# SW6106_A_A_B_C_MCU_SEG.net
KiCad netlist of a schematic drawn in Altium Designer
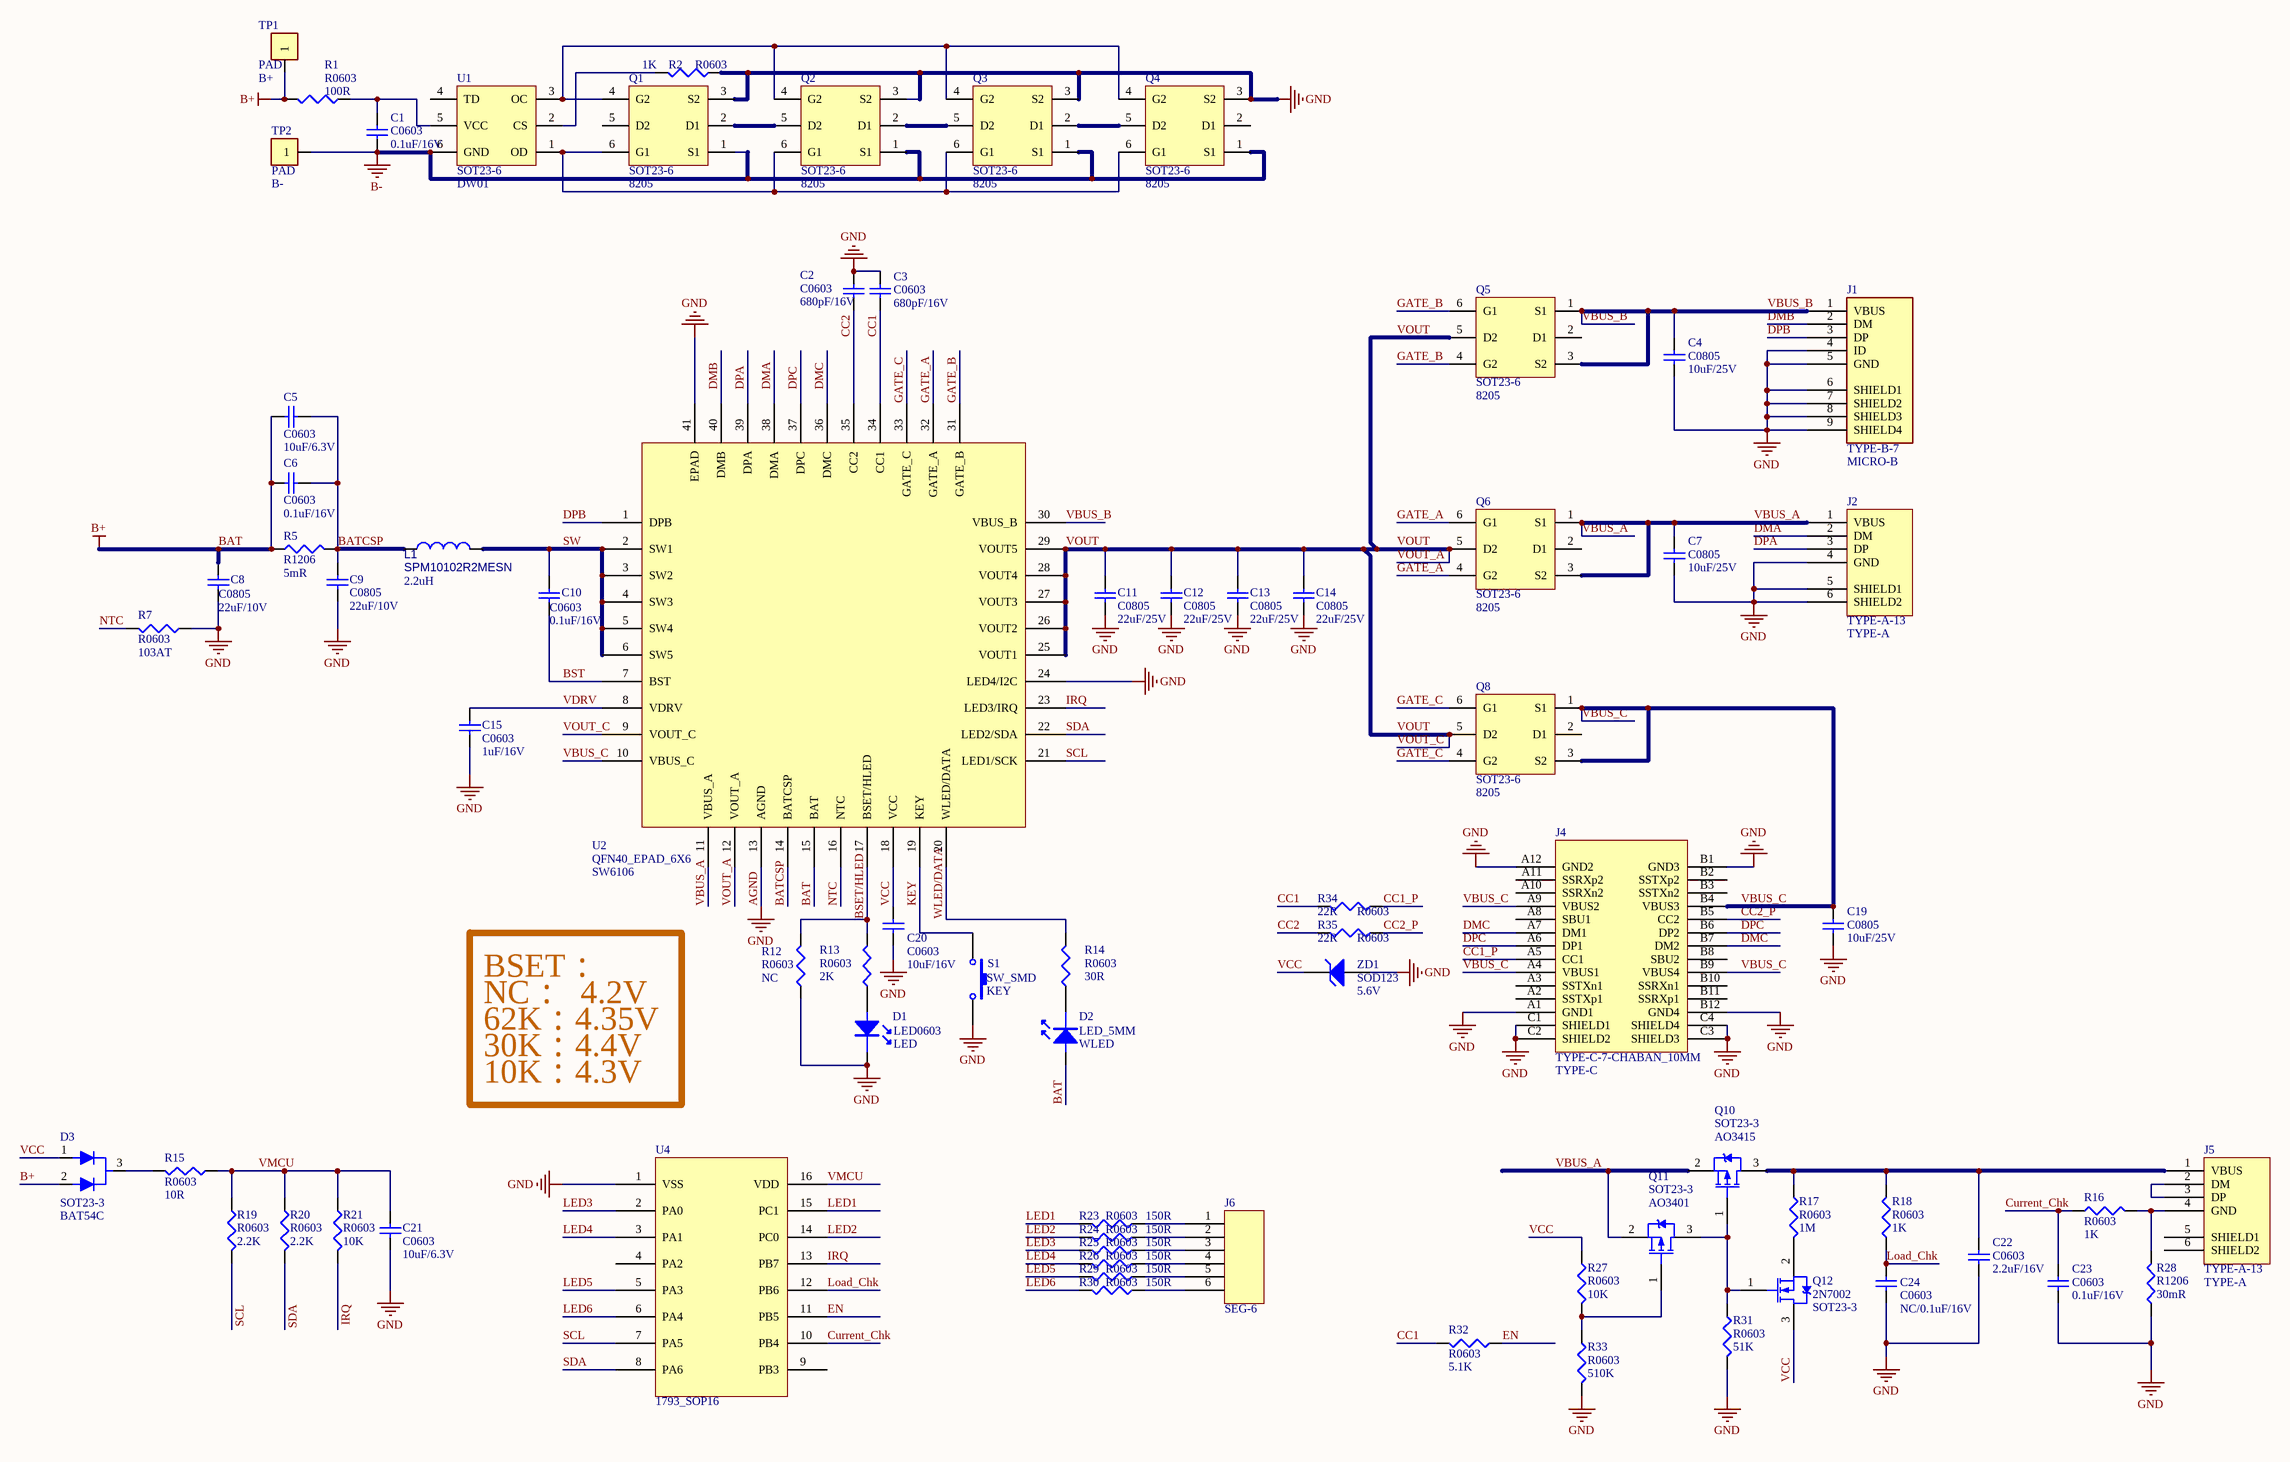
[diagram p0: SW6106+A+A+B+C+MCU+SEG.SchDoc]

(export (version "E")
  (design (tool "Eeschema 10.0.6"))
  (components
    (comp (ref "C1")
      (value "C0603")
      (footprint "C0603")
      (description "Capacitor")
      (fields (field (name "ALTIUM_VALUE") "0.1uF/16V") (field (name "PUBLISHER") "Altium Limited"))
      (libsource (lib "*") (part "Cap"))
    )
    (comp (ref "C2")
      (value "C0603")
      (footprint "C0603")
      (description "Capacitor")
      (fields (field (name "ALTIUM_VALUE") "680pF/16V") (field (name "PUBLISHER") "Altium Limited"))
      (libsource (lib "*") (part "CAP0603"))
    )
    (comp (ref "C3")
      (value "C0603")
      (footprint "C0603")
      (description "Capacitor")
      (fields (field (name "ALTIUM_VALUE") "680pF/16V") (field (name "PUBLISHER") "Altium Limited"))
      (libsource (lib "*") (part "CAP0603"))
    )
    (comp (ref "C4")
      (value "C0805")
      (footprint "C0805")
      (description "Capacitor")
      (fields (field (name "ALTIUM_VALUE") "10uF/25V") (field (name "PUBLISHER") "Altium Limited"))
      (libsource (lib "*") (part "CAP0603"))
    )
    (comp (ref "C5")
      (value "C0603")
      (footprint "C0603")
      (description "Capacitor")
      (fields (field (name "ALTIUM_VALUE") "10uF/6.3V") (field (name "PUBLISHER") "Altium Limited"))
      (libsource (lib "*") (part "CAP0603"))
    )
    (comp (ref "C6")
      (value "C0603")
      (footprint "C0603")
      (description "Capacitor")
      (fields (field (name "ALTIUM_VALUE") "0.1uF/16V") (field (name "PUBLISHER") "Altium Limited"))
      (libsource (lib "*") (part "CAP0603"))
    )
    (comp (ref "C7")
      (value "C0805")
      (footprint "C0805")
      (description "Capacitor")
      (fields (field (name "ALTIUM_VALUE") "10uF/25V") (field (name "PUBLISHER") "Altium Limited"))
      (libsource (lib "*") (part "CAP0603"))
    )
    (comp (ref "C8")
      (value "C0805")
      (footprint "C0805")
      (description "Capacitor")
      (fields (field (name "ALTIUM_VALUE") "22uF/10V") (field (name "PUBLISHER") "Altium Limited"))
      (libsource (lib "*") (part "CAP0805"))
    )
    (comp (ref "C9")
      (value "C0805")
      (footprint "C0805")
      (description "Capacitor")
      (fields (field (name "ALTIUM_VALUE") "22uF/10V") (field (name "PUBLISHER") "Altium Limited"))
      (libsource (lib "*") (part "CAP0805"))
    )
    (comp (ref "C10")
      (value "C0603")
      (footprint "C0603")
      (description "Capacitor")
      (fields (field (name "ALTIUM_VALUE") "0.1uF/16V") (field (name "PUBLISHER") "Altium Limited"))
      (libsource (lib "*") (part "CAP0603"))
    )
    (comp (ref "C11")
      (value "C0805")
      (footprint "C0805")
      (description "Capacitor")
      (fields (field (name "ALTIUM_VALUE") "22uF/25V") (field (name "PUBLISHER") "Altium Limited"))
      (libsource (lib "*") (part "CAP0805"))
    )
    (comp (ref "C12")
      (value "C0805")
      (footprint "C0805")
      (description "Capacitor")
      (fields (field (name "ALTIUM_VALUE") "22uF/25V") (field (name "PUBLISHER") "Altium Limited"))
      (libsource (lib "*") (part "CAP0805"))
    )
    (comp (ref "C13")
      (value "C0805")
      (footprint "C0805")
      (description "Capacitor")
      (fields (field (name "ALTIUM_VALUE") "22uF/25V") (field (name "PUBLISHER") "Altium Limited"))
      (libsource (lib "*") (part "CAP0805"))
    )
    (comp (ref "C14")
      (value "C0805")
      (footprint "C0805")
      (description "Capacitor")
      (fields (field (name "ALTIUM_VALUE") "22uF/25V") (field (name "PUBLISHER") "Altium Limited"))
      (libsource (lib "*") (part "CAP0805"))
    )
    (comp (ref "C15")
      (value "C0603")
      (footprint "C0603")
      (description "Capacitor")
      (fields (field (name "ALTIUM_VALUE") "1uF/16V") (field (name "PUBLISHER") "Altium Limited"))
      (libsource (lib "*") (part "CAP0603"))
    )
    (comp (ref "C19")
      (value "C0805")
      (footprint "C0805")
      (description "Capacitor")
      (fields (field (name "ALTIUM_VALUE") "10uF/25V") (field (name "PUBLISHER") "Altium Limited"))
      (libsource (lib "*") (part "CAP0603"))
    )
    (comp (ref "C20")
      (value "C0603")
      (footprint "C0603")
      (description "Capacitor")
      (fields (field (name "ALTIUM_VALUE") "10uF/16V") (field (name "PUBLISHER") "Altium Limited"))
      (libsource (lib "*") (part "CAP0603"))
    )
    (comp (ref "C21")
      (value "C0603")
      (footprint "C0603")
      (description "Capacitor")
      (fields (field (name "ALTIUM_VALUE") "10uF/6.3V") (field (name "PUBLISHER") "Altium Limited"))
      (libsource (lib "*") (part "CAP0603"))
    )
    (comp (ref "C22")
      (value "C0603")
      (footprint "C0603")
      (description "Capacitor")
      (fields (field (name "ALTIUM_VALUE") "2.2uF/16V") (field (name "PUBLISHER") "Altium Limited"))
      (libsource (lib "*") (part "CAP0603"))
    )
    (comp (ref "C23")
      (value "C0603")
      (footprint "C0603")
      (description "Capacitor")
      (fields (field (name "ALTIUM_VALUE") "0.1uF/16V") (field (name "PUBLISHER") "Altium Limited"))
      (libsource (lib "*") (part "CAP0603"))
    )
    (comp (ref "C24")
      (value "C0603")
      (footprint "C0603")
      (description "Capacitor")
      (fields (field (name "ALTIUM_VALUE") "NC/0.1uF/16V") (field (name "PUBLISHER") "Altium Limited"))
      (libsource (lib "*") (part "CAP0603"))
    )
    (comp (ref "D1") (value "LED") (footprint "LED0603") (libsource (lib "*") (part "LED")))
    (comp (ref "D2")
      (value "WLED")
      (footprint "LED_5MM")
      (fields (field (name "FOOTPRINF") "LED_5MM") (field (name "Comment") "LED_5MM"))
      (libsource (lib "*") (part "LED"))
    )
    (comp (ref "D3") (value "BAT54C") (footprint "SOT23-3") (libsource (lib "Schlib1-2012") (part "D3")))
    (comp (ref "J1")
      (value "MICRO-B")
      (footprint "TYPE-B-7")
      (fields (field (name "FOOTPRINTF") "TYPE-B-7") (field (name "Comment") "USB_MICRO_B"))
      (libsource (lib "*") (part "USB_MICRO_B"))
    )
    (comp (ref "J2")
      (value "TYPE-A")
      (footprint "TYPE-A-13")
      (fields (field (name "FOOTPRINF") "TYPE-A-13") (field (name "Comment") "TYPE-A-1"))
      (libsource (lib "*") (part "TYPE-A-1"))
    )
    (comp (ref "J4")
      (value "TYPE-C")
      (footprint "TYPE-C-7-CHABAN_10MM")
      (libsource (lib "*") (part "TYPE-C"))
    )
    (comp (ref "J5")
      (value "TYPE-A")
      (footprint "PIE10-USB")
      (fields (field (name "FOOTPRINF") "TYPE-A-13") (field (name "Comment") "TYPE-A-1"))
      (libsource (lib "*") (part "TYPE-A-1"))
    )
    (comp (ref "J6") (value "SEG-6") (libsource (lib "TEST") (part "LCD-6")))
    (comp (ref "L1")
      (value "SPM10102R2MESN")
      (footprint "INDUCTOR_SPM1010")
      (fields (field (name "ALTIUM_VALUE") "2.2uH"))
      (libsource (lib "*") (part "INDUCTOR"))
    )
    (comp (ref "Q1")
      (value "8205")
      (footprint "SOT23-6")
      (fields (field (name "FOOTPRINF") "SOT23-6"))
      (libsource (lib "") (part "8205B_1"))
    )
    (comp (ref "Q2")
      (value "8205")
      (footprint "SOT23-6")
      (fields (field (name "FOOTPRINF") "SOT23-6"))
      (libsource (lib "") (part "8205B_1"))
    )
    (comp (ref "Q3")
      (value "8205")
      (footprint "SOT23-6")
      (fields (field (name "FOOTPRINF") "SOT23-6"))
      (libsource (lib "") (part "8205B_1"))
    )
    (comp (ref "Q4")
      (value "8205")
      (footprint "SOT23-6")
      (fields (field (name "FOOTPRINF") "SOT23-6"))
      (libsource (lib "") (part "8205B_1"))
    )
    (comp (ref "Q5")
      (value "8205")
      (footprint "SOT23-6")
      (fields (field (name "FOOTPRINF") "SOT23-6"))
      (libsource (lib "*") (part "8205B"))
    )
    (comp (ref "Q6")
      (value "8205")
      (footprint "SOT23-6")
      (fields (field (name "FOOTPRINF") "SOT23-6"))
      (libsource (lib "*") (part "8205B"))
    )
    (comp (ref "Q8")
      (value "8205")
      (footprint "SOT23-6")
      (fields (field (name "FOOTPRINF") "SOT23-6"))
      (libsource (lib "*") (part "8205B"))
    )
    (comp (ref "Q10")
      (value "AO3415")
      (footprint "SOT23-3")
      (description "P-Channel Power MOSFET")
      (fields (field (name "Comment") "PMOS-2") (field (name "PUBLISHER") "Altium Limited"))
      (libsource (lib "Miscellaneous Devices") (part "PMOS-2"))
    )
    (comp (ref "Q11")
      (value "AO3401")
      (footprint "SOT23-3")
      (description "P-Channel Power MOSFET")
      (fields (field (name "Comment") "PMOS-2") (field (name "PUBLISHER") "Altium Limited"))
      (libsource (lib "Miscellaneous Devices") (part "PMOS-2"))
    )
    (comp (ref "Q12")
      (value "2N7002")
      (footprint "SOT23-3")
      (description "N-Channel Power MOSFET")
      (fields (field (name "Comment") "NMOS-2") (field (name "PUBLISHER") "Altium Limited"))
      (libsource (lib "Miscellaneous Devices") (part "NMOS-2"))
    )
    (comp (ref "R1")
      (value "R0603")
      (footprint "R0603")
      (description "Resistor")
      (fields (field (name "ALTIUM_VALUE") "100R") (field (name "PUBLISHER") "Altium Limited"))
      (libsource (lib "*") (part "Res3"))
    )
    (comp (ref "R2")
      (value "R0603")
      (footprint "R0603")
      (description "Resistor")
      (fields (field (name "ALTIUM_VALUE") "1K") (field (name "PUBLISHER") "Altium Limited"))
      (libsource (lib "*") (part "Res3"))
    )
    (comp (ref "R5")
      (value "R1206")
      (footprint "R1206")
      (description "Resistor")
      (fields (field (name "ALTIUM_VALUE") "5mR") (field (name "PUBLISHER") "Altium Limited"))
      (libsource (lib "*") (part "RES"))
    )
    (comp (ref "R7")
      (value "R0603")
      (footprint "R0603")
      (description "Resistor")
      (fields (field (name "ALTIUM_VALUE") "103AT") (field (name "PUBLISHER") "Altium Limited"))
      (libsource (lib "*") (part "RES"))
    )
    (comp (ref "R12")
      (value "R0603")
      (footprint "R0603")
      (description "Resistor")
      (fields (field (name "ALTIUM_VALUE") "NC") (field (name "PUBLISHER") "Altium Limited"))
      (libsource (lib "*") (part "RES"))
    )
    (comp (ref "R13")
      (value "R0603")
      (footprint "R0603")
      (description "Resistor")
      (fields (field (name "ALTIUM_VALUE") "2K") (field (name "PUBLISHER") "Altium Limited"))
      (libsource (lib "*") (part "RES"))
    )
    (comp (ref "R14")
      (value "R0603")
      (footprint "R0603")
      (description "Resistor")
      (fields (field (name "ALTIUM_VALUE") "30R") (field (name "PUBLISHER") "Altium Limited"))
      (libsource (lib "*") (part "RES"))
    )
    (comp (ref "R15")
      (value "R0603")
      (footprint "R0603")
      (description "Resistor")
      (fields (field (name "ALTIUM_VALUE") "10R") (field (name "PUBLISHER") "Altium Limited"))
      (libsource (lib "*") (part "RES"))
    )
    (comp (ref "R16")
      (value "R0603")
      (footprint "R0603")
      (description "Resistor")
      (fields (field (name "ALTIUM_VALUE") "1K") (field (name "PUBLISHER") "Altium Limited"))
      (libsource (lib "*") (part "RES"))
    )
    (comp (ref "R17")
      (value "R0603")
      (footprint "R0603")
      (description "Resistor")
      (fields (field (name "ALTIUM_VALUE") "1M") (field (name "PUBLISHER") "Altium Limited"))
      (libsource (lib "*") (part "RES"))
    )
    (comp (ref "R18")
      (value "R0603")
      (footprint "R0603")
      (description "Resistor")
      (fields (field (name "ALTIUM_VALUE") "1K") (field (name "PUBLISHER") "Altium Limited"))
      (libsource (lib "*") (part "RES"))
    )
    (comp (ref "R19")
      (value "R0603")
      (footprint "R0603")
      (description "Resistor")
      (fields (field (name "ALTIUM_VALUE") "2.2K") (field (name "PUBLISHER") "Altium Limited"))
      (libsource (lib "*") (part "RES"))
    )
    (comp (ref "R20")
      (value "R0603")
      (footprint "R0603")
      (description "Resistor")
      (fields (field (name "ALTIUM_VALUE") "2.2K") (field (name "PUBLISHER") "Altium Limited"))
      (libsource (lib "*") (part "RES"))
    )
    (comp (ref "R21")
      (value "R0603")
      (footprint "R0603")
      (description "Resistor")
      (fields (field (name "ALTIUM_VALUE") "10K") (field (name "PUBLISHER") "Altium Limited"))
      (libsource (lib "*") (part "RES"))
    )
    (comp (ref "R23")
      (value "R0603")
      (footprint "R0603")
      (description "Resistor")
      (fields (field (name "ALTIUM_VALUE") "150R") (field (name "PUBLISHER") "Altium Limited"))
      (libsource (lib "*") (part "RES"))
    )
    (comp (ref "R24")
      (value "R0603")
      (footprint "R0603")
      (description "Resistor")
      (fields (field (name "ALTIUM_VALUE") "150R") (field (name "PUBLISHER") "Altium Limited"))
      (libsource (lib "*") (part "RES"))
    )
    (comp (ref "R25")
      (value "R0603")
      (footprint "R0603")
      (description "Resistor")
      (fields (field (name "ALTIUM_VALUE") "150R") (field (name "PUBLISHER") "Altium Limited"))
      (libsource (lib "*") (part "RES"))
    )
    (comp (ref "R26")
      (value "R0603")
      (footprint "R0603")
      (description "Resistor")
      (fields (field (name "ALTIUM_VALUE") "150R") (field (name "PUBLISHER") "Altium Limited"))
      (libsource (lib "*") (part "RES"))
    )
    (comp (ref "R27")
      (value "R0603")
      (footprint "R0603")
      (description "Resistor")
      (fields (field (name "ALTIUM_VALUE") "10K") (field (name "PUBLISHER") "Altium Limited"))
      (libsource (lib "*") (part "RES"))
    )
    (comp (ref "R28")
      (value "R1206")
      (footprint "C-1206A")
      (description "Resistor")
      (fields (field (name "ALTIUM_VALUE") "30mR") (field (name "PUBLISHER") "Altium Limited"))
      (libsource (lib "*") (part "RES"))
    )
    (comp (ref "R29")
      (value "R0603")
      (footprint "R0603")
      (description "Resistor")
      (fields (field (name "ALTIUM_VALUE") "150R") (field (name "PUBLISHER") "Altium Limited"))
      (libsource (lib "*") (part "RES"))
    )
    (comp (ref "R30")
      (value "R0603")
      (footprint "R0603")
      (description "Resistor")
      (fields (field (name "ALTIUM_VALUE") "150R") (field (name "PUBLISHER") "Altium Limited"))
      (libsource (lib "*") (part "RES"))
    )
    (comp (ref "R31")
      (value "R0603")
      (footprint "R0603")
      (description "Resistor")
      (fields (field (name "ALTIUM_VALUE") "51K") (field (name "PUBLISHER") "Altium Limited"))
      (libsource (lib "*") (part "RES"))
    )
    (comp (ref "R32")
      (value "R0603")
      (footprint "R0603")
      (description "Resistor")
      (fields (field (name "ALTIUM_VALUE") "5.1K") (field (name "PUBLISHER") "Altium Limited"))
      (libsource (lib "*") (part "RES"))
    )
    (comp (ref "R33")
      (value "R0603")
      (footprint "R0603")
      (description "Resistor")
      (fields (field (name "ALTIUM_VALUE") "510K") (field (name "PUBLISHER") "Altium Limited"))
      (libsource (lib "*") (part "RES"))
    )
    (comp (ref "R34")
      (value "R0603")
      (footprint "R0603")
      (description "Resistor")
      (fields (field (name "ALTIUM_VALUE") "22R") (field (name "PUBLISHER") "Altium Limited"))
      (libsource (lib "*") (part "RES"))
    )
    (comp (ref "R35")
      (value "R0603")
      (footprint "R0603")
      (description "Resistor")
      (fields (field (name "ALTIUM_VALUE") "22R") (field (name "PUBLISHER") "Altium Limited"))
      (libsource (lib "*") (part "RES"))
    )
    (comp (ref "S1")
      (value "KEY")
      (footprint "SW_SMD")
      (fields (field (name "FOOTPRINF") "SW_SMD"))
      (libsource (lib "*") (part "SW K"))
    )
    (comp (ref "TP1") (value "B+") (footprint "PAD") (libsource (lib "*") (part "Test Point")))
    (comp (ref "TP2") (value "B-") (footprint "PAD") (libsource (lib "") (part "Test Point_1")))
    (comp (ref "U1")
      (value "DW01")
      (footprint "SOT23-6")
      (fields (field (name "FOOTPRINF") "SOT23-6"))
      (libsource (lib "*") (part "DW01"))
    )
    (comp (ref "U2")
      (value "SW6106")
      (footprint "QFN40_EPAD_6X6")
      (libsource (lib "TEST") (part "SW6106_AFC"))
    )
    (comp (ref "U4") (value "1793_SOP16") (libsource (lib "TEST") (part "1793_SOP16")))
    (comp (ref "ZD1")
      (value "SOD123")
      (footprint "SOD-123")
      (description "Zener Diode")
      (fields (field (name "ALTIUM_UNNAMED_1") "5.6V"))
      (libsource (lib "Miscellaneous Devices") (part "D Zener"))
    )
  )
  (nets
    (net (code "1") (name "/BATCSP") (class "Default")
      (node (ref "C5") (pin "2") (pinfunction "2_2") (pintype "passive"))
      (node (ref "C6") (pin "2") (pinfunction "2_2") (pintype "passive"))
      (node (ref "C9") (pin "2") (pinfunction "2_2") (pintype "passive"))
      (node (ref "L1") (pin "1") (pinfunction "1_1") (pintype "passive"))
      (node (ref "R5") (pin "2") (pinfunction "2_2") (pintype "passive"))
      (node (ref "U2") (pin "14") (pinfunction "BATCSP_14") (pintype "passive"))
    )
    (net (code "2") (name "/BSET{slash}HLED") (class "Default")
      (node (ref "R12") (pin "2") (pinfunction "2_2") (pintype "passive"))
      (node (ref "R13") (pin "2") (pinfunction "2_2") (pintype "passive"))
      (node (ref "U2") (pin "17") (pinfunction "BSET/HLED_17") (pintype "passive"))
    )
    (net (code "3") (name "/BST") (class "Default")
      (node (ref "C10") (pin "1") (pinfunction "1_1") (pintype "passive"))
      (node (ref "U2") (pin "7") (pinfunction "BST_7") (pintype "passive"))
    )
    (net (code "4") (name "/CC1") (class "Default")
      (node (ref "C3") (pin "1") (pinfunction "1_1") (pintype "passive"))
      (node (ref "R32") (pin "2") (pinfunction "2_2") (pintype "passive"))
      (node (ref "R34") (pin "2") (pinfunction "2_2") (pintype "passive"))
      (node (ref "U2") (pin "34") (pinfunction "CC1_34") (pintype "passive"))
    )
    (net (code "5") (name "/CC1_P") (class "Default")
      (node (ref "J4") (pin "A5") (pinfunction "CC1_A5") (pintype "passive"))
      (node (ref "R34") (pin "1") (pinfunction "1_1") (pintype "passive"))
    )
    (net (code "6") (name "/CC2") (class "Default")
      (node (ref "C2") (pin "1") (pinfunction "1_1") (pintype "passive"))
      (node (ref "R35") (pin "2") (pinfunction "2_2") (pintype "passive"))
      (node (ref "U2") (pin "35") (pinfunction "CC2_35") (pintype "passive"))
    )
    (net (code "7") (name "/CC2_P") (class "Default")
      (node (ref "J4") (pin "B5") (pinfunction "CC2_B5") (pintype "passive"))
      (node (ref "R35") (pin "1") (pinfunction "1_1") (pintype "passive"))
    )
    (net (code "8") (name "/Current_Chk") (class "Default")
      (node (ref "C23") (pin "2") (pinfunction "2_2") (pintype "passive"))
      (node (ref "R16") (pin "1") (pinfunction "1_1") (pintype "passive"))
      (node (ref "U4") (pin "10") (pinfunction "PB4_10") (pintype "passive"))
    )
    (net (code "9") (name "/DMA") (class "Default")
      (node (ref "J2") (pin "2") (pinfunction "DM_2") (pintype "passive"))
      (node (ref "U2") (pin "38") (pinfunction "DMA_38") (pintype "passive"))
    )
    (net (code "10") (name "/DMB") (class "Default")
      (node (ref "J1") (pin "2") (pinfunction "DM_2") (pintype "passive"))
      (node (ref "U2") (pin "40") (pinfunction "DMB_40") (pintype "passive"))
    )
    (net (code "11") (name "/DMC") (class "Default")
      (node (ref "J4") (pin "A7") (pinfunction "DM1_A7") (pintype "passive"))
      (node (ref "J4") (pin "B7") (pinfunction "DM2_B7") (pintype "passive"))
      (node (ref "U2") (pin "36") (pinfunction "DMC_36") (pintype "passive"))
    )
    (net (code "12") (name "/DPA") (class "Default")
      (node (ref "J2") (pin "3") (pinfunction "DP_3") (pintype "passive"))
      (node (ref "U2") (pin "39") (pinfunction "DPA_39") (pintype "passive"))
    )
    (net (code "13") (name "/DPB") (class "Default")
      (node (ref "J1") (pin "3") (pinfunction "DP_3") (pintype "passive"))
      (node (ref "U2") (pin "1") (pinfunction "DPB_1") (pintype "passive"))
    )
    (net (code "14") (name "/DPC") (class "Default")
      (node (ref "J4") (pin "A6") (pinfunction "DP1_A6") (pintype "passive"))
      (node (ref "J4") (pin "B6") (pinfunction "DP2_B6") (pintype "passive"))
      (node (ref "U2") (pin "37") (pinfunction "DPC_37") (pintype "passive"))
    )
    (net (code "15") (name "/EN") (class "Default")
      (node (ref "R32") (pin "1") (pinfunction "1_1") (pintype "passive"))
      (node (ref "U4") (pin "11") (pinfunction "PB5_11") (pintype "passive"))
    )
    (net (code "16") (name "/GATE_A") (class "Default")
      (node (ref "Q6") (pin "4") (pinfunction "G2_4") (pintype "passive"))
      (node (ref "Q6") (pin "6") (pinfunction "G1_6") (pintype "passive"))
      (node (ref "U2") (pin "32") (pinfunction "GATE_A_32") (pintype "passive"))
    )
    (net (code "17") (name "/GATE_B") (class "Default")
      (node (ref "Q5") (pin "4") (pinfunction "G2_4") (pintype "passive"))
      (node (ref "Q5") (pin "6") (pinfunction "G1_6") (pintype "passive"))
      (node (ref "U2") (pin "31") (pinfunction "GATE_B_31") (pintype "passive"))
    )
    (net (code "18") (name "/GATE_C") (class "Default")
      (node (ref "Q8") (pin "4") (pinfunction "G2_4") (pintype "passive"))
      (node (ref "Q8") (pin "6") (pinfunction "G1_6") (pintype "passive"))
      (node (ref "U2") (pin "33") (pinfunction "GATE_C_33") (pintype "passive"))
    )
    (net (code "19") (name "/IRQ") (class "Default")
      (node (ref "R21") (pin "2") (pinfunction "2_2") (pintype "passive"))
      (node (ref "U2") (pin "23") (pinfunction "LED3/IRQ_23") (pintype "passive"))
      (node (ref "U4") (pin "13") (pinfunction "PB7_13") (pintype "passive"))
    )
    (net (code "20") (name "/KEY") (class "Default")
      (node (ref "S1") (pin "1") (pinfunction "1_1") (pintype "passive"))
      (node (ref "U2") (pin "19") (pinfunction "KEY_19") (pintype "passive"))
    )
    (net (code "21") (name "/LED1") (class "Default")
      (node (ref "R23") (pin "2") (pinfunction "2_2") (pintype "passive"))
      (node (ref "U4") (pin "15") (pinfunction "PC1_15") (pintype "passive"))
    )
    (net (code "22") (name "/LED2") (class "Default")
      (node (ref "R24") (pin "2") (pinfunction "2_2") (pintype "passive"))
      (node (ref "U4") (pin "14") (pinfunction "PC0_14") (pintype "passive"))
    )
    (net (code "23") (name "/LED3") (class "Default")
      (node (ref "R25") (pin "2") (pinfunction "2_2") (pintype "passive"))
      (node (ref "U4") (pin "2") (pinfunction "PA0_2") (pintype "passive"))
    )
    (net (code "24") (name "/LED4") (class "Default")
      (node (ref "R26") (pin "2") (pinfunction "2_2") (pintype "passive"))
      (node (ref "U4") (pin "3") (pinfunction "PA1_3") (pintype "passive"))
    )
    (net (code "25") (name "/LED5") (class "Default")
      (node (ref "R29") (pin "2") (pinfunction "2_2") (pintype "passive"))
      (node (ref "U4") (pin "5") (pinfunction "PA3_5") (pintype "passive"))
    )
    (net (code "26") (name "/LED6") (class "Default")
      (node (ref "R30") (pin "2") (pinfunction "2_2") (pintype "passive"))
      (node (ref "U4") (pin "6") (pinfunction "PA4_6") (pintype "passive"))
    )
    (net (code "27") (name "/Load_Chk") (class "Default")
      (node (ref "C24") (pin "2") (pinfunction "2_2") (pintype "passive"))
      (node (ref "R18") (pin "1") (pinfunction "1_1") (pintype "passive"))
      (node (ref "U4") (pin "12") (pinfunction "PB6_12") (pintype "passive"))
    )
    (net (code "28") (name "/NTC") (class "Default")
      (node (ref "R7") (pin "2") (pinfunction "2_2") (pintype "passive"))
      (node (ref "U2") (pin "16") (pinfunction "NTC_16") (pintype "passive"))
    )
    (net (code "29") (name "/SCL") (class "Default")
      (node (ref "R19") (pin "2") (pinfunction "2_2") (pintype "passive"))
      (node (ref "U2") (pin "21") (pinfunction "LED1/SCK_21") (pintype "passive"))
      (node (ref "U4") (pin "7") (pinfunction "PA5_7") (pintype "passive"))
    )
    (net (code "30") (name "/SDA") (class "Default")
      (node (ref "R20") (pin "2") (pinfunction "2_2") (pintype "passive"))
      (node (ref "U2") (pin "22") (pinfunction "LED2/SDA_22") (pintype "passive"))
      (node (ref "U4") (pin "8") (pinfunction "PA6_8") (pintype "passive"))
    )
    (net (code "31") (name "/SW") (class "Default")
      (node (ref "C10") (pin "2") (pinfunction "2_2") (pintype "passive"))
      (node (ref "L1") (pin "2") (pinfunction "2_2") (pintype "passive"))
      (node (ref "U2") (pin "2") (pinfunction "SW1_2") (pintype "passive"))
      (node (ref "U2") (pin "3") (pinfunction "SW2_3") (pintype "passive"))
      (node (ref "U2") (pin "4") (pinfunction "SW3_4") (pintype "passive"))
      (node (ref "U2") (pin "5") (pinfunction "SW4_5") (pintype "passive"))
      (node (ref "U2") (pin "6") (pinfunction "SW5_6") (pintype "passive"))
    )
    (net (code "32") (name "/VBUS_A") (class "Default")
      (node (ref "C7") (pin "2") (pinfunction "2_2") (pintype "passive"))
      (node (ref "J2") (pin "1") (pinfunction "VBUS_1") (pintype "passive"))
      (node (ref "Q10") (pin "2") (pinfunction "S_2") (pintype "passive"))
      (node (ref "Q11") (pin "2") (pinfunction "S_2") (pintype "passive"))
      (node (ref "Q6") (pin "1") (pinfunction "S1_1") (pintype "passive"))
      (node (ref "Q6") (pin "3") (pinfunction "S2_3") (pintype "passive"))
      (node (ref "U2") (pin "11") (pinfunction "VBUS_A_11") (pintype "passive"))
    )
    (net (code "33") (name "/VBUS_B") (class "Default")
      (node (ref "C4") (pin "2") (pinfunction "2_2") (pintype "passive"))
      (node (ref "J1") (pin "1") (pinfunction "VBUS_1") (pintype "passive"))
      (node (ref "Q5") (pin "1") (pinfunction "S1_1") (pintype "passive"))
      (node (ref "Q5") (pin "3") (pinfunction "S2_3") (pintype "passive"))
      (node (ref "U2") (pin "30") (pinfunction "VBUS_B_30") (pintype "passive"))
    )
    (net (code "34") (name "/VBUS_C") (class "Default")
      (node (ref "C19") (pin "2") (pinfunction "2_2") (pintype "passive"))
      (node (ref "J4") (pin "A4") (pinfunction "VBUS1_A4") (pintype "passive"))
      (node (ref "J4") (pin "A9") (pinfunction "VBUS2_A9") (pintype "passive"))
      (node (ref "J4") (pin "B4") (pinfunction "VBUS3_B4") (pintype "passive"))
      (node (ref "J4") (pin "B9") (pinfunction "VBUS4_B9") (pintype "passive"))
      (node (ref "Q8") (pin "1") (pinfunction "S1_1") (pintype "passive"))
      (node (ref "Q8") (pin "3") (pinfunction "S2_3") (pintype "passive"))
      (node (ref "U2") (pin "10") (pinfunction "VBUS_C_10") (pintype "passive"))
    )
    (net (code "35") (name "/VCC") (class "Default")
      (node (ref "C20") (pin "2") (pinfunction "2_2") (pintype "passive"))
      (node (ref "D3") (pin "1") (pintype "passive"))
      (node (ref "Q12") (pin "3") (pinfunction "D_3") (pintype "passive"))
      (node (ref "R27") (pin "1") (pinfunction "1_1") (pintype "passive"))
      (node (ref "U2") (pin "18") (pinfunction "VCC_18") (pintype "passive"))
      (node (ref "ZD1") (pin "2") (pinfunction "K_2") (pintype "passive"))
    )
    (net (code "36") (name "/VDRV") (class "Default")
      (node (ref "C15") (pin "2") (pinfunction "2_2") (pintype "passive"))
      (node (ref "U2") (pin "8") (pinfunction "VDRV_8") (pintype "passive"))
    )
    (net (code "37") (name "/VMCU") (class "Default")
      (node (ref "C21") (pin "1") (pinfunction "1_1") (pintype "passive"))
      (node (ref "R15") (pin "1") (pinfunction "1_1") (pintype "passive"))
      (node (ref "R19") (pin "1") (pinfunction "1_1") (pintype "passive"))
      (node (ref "R20") (pin "1") (pinfunction "1_1") (pintype "passive"))
      (node (ref "R21") (pin "1") (pinfunction "1_1") (pintype "passive"))
      (node (ref "U4") (pin "16") (pinfunction "VDD_16") (pintype "passive"))
    )
    (net (code "38") (name "/VOUT") (class "Default")
      (node (ref "C11") (pin "2") (pinfunction "2_2") (pintype "passive"))
      (node (ref "C12") (pin "2") (pinfunction "2_2") (pintype "passive"))
      (node (ref "C13") (pin "2") (pinfunction "2_2") (pintype "passive"))
      (node (ref "C14") (pin "2") (pinfunction "2_2") (pintype "passive"))
      (node (ref "Q5") (pin "5") (pinfunction "D2_5") (pintype "passive"))
      (node (ref "Q6") (pin "5") (pinfunction "D2_5") (pintype "passive"))
      (node (ref "Q8") (pin "5") (pinfunction "D2_5") (pintype "passive"))
      (node (ref "U2") (pin "12") (pinfunction "VOUT_A_12") (pintype "passive"))
      (node (ref "U2") (pin "25") (pinfunction "VOUT1_25") (pintype "passive"))
      (node (ref "U2") (pin "26") (pinfunction "VOUT2_26") (pintype "passive"))
      (node (ref "U2") (pin "27") (pinfunction "VOUT3_27") (pintype "passive"))
      (node (ref "U2") (pin "28") (pinfunction "VOUT4_28") (pintype "passive"))
      (node (ref "U2") (pin "29") (pinfunction "VOUT5_29") (pintype "passive"))
      (node (ref "U2") (pin "9") (pinfunction "VOUT_C_9") (pintype "passive"))
    )
    (net (code "39") (name "/WLED{slash}DATA") (class "Default")
      (node (ref "R14") (pin "2") (pinfunction "2_2") (pintype "passive"))
      (node (ref "U2") (pin "20") (pinfunction "WLED/DATA_20") (pintype "passive"))
    )
    (net (code "40") (name "B+") (class "Default")
      (node (ref "C5") (pin "1") (pinfunction "1_1") (pintype "passive"))
      (node (ref "C6") (pin "1") (pinfunction "1_1") (pintype "passive"))
      (node (ref "C8") (pin "2") (pinfunction "2_2") (pintype "passive"))
      (node (ref "D2") (pin "1") (pinfunction "A_1") (pintype "passive"))
      (node (ref "D3") (pin "2") (pintype "passive"))
      (node (ref "R1") (pin "2") (pinfunction "2_2") (pintype "passive"))
      (node (ref "R5") (pin "1") (pinfunction "1_1") (pintype "passive"))
      (node (ref "TP1") (pin "1") (pinfunction "1_1") (pintype "passive"))
      (node (ref "U2") (pin "15") (pinfunction "BAT_15") (pintype "passive"))
    )
    (net (code "41") (name "B-") (class "Default")
      (node (ref "C1") (pin "1") (pinfunction "1_1") (pintype "passive"))
      (node (ref "Q1") (pin "1") (pinfunction "S1_1") (pintype "passive"))
      (node (ref "Q2") (pin "1") (pinfunction "S1_1") (pintype "passive"))
      (node (ref "Q3") (pin "1") (pinfunction "S1_1") (pintype "passive"))
      (node (ref "Q4") (pin "1") (pinfunction "S1_1") (pintype "passive"))
      (node (ref "TP2") (pin "1") (pinfunction "1_1") (pintype "passive"))
      (node (ref "U1") (pin "6") (pinfunction "GND_6") (pintype "passive"))
    )
    (net (code "42") (name "GND") (class "Default")
      (node (ref "C11") (pin "1") (pinfunction "1_1") (pintype "passive"))
      (node (ref "C12") (pin "1") (pinfunction "1_1") (pintype "passive"))
      (node (ref "C13") (pin "1") (pinfunction "1_1") (pintype "passive"))
      (node (ref "C14") (pin "1") (pinfunction "1_1") (pintype "passive"))
      (node (ref "C15") (pin "1") (pinfunction "1_1") (pintype "passive"))
      (node (ref "C19") (pin "1") (pinfunction "1_1") (pintype "passive"))
      (node (ref "C2") (pin "2") (pinfunction "2_2") (pintype "passive"))
      (node (ref "C20") (pin "1") (pinfunction "1_1") (pintype "passive"))
      (node (ref "C21") (pin "2") (pinfunction "2_2") (pintype "passive"))
      (node (ref "C22") (pin "1") (pinfunction "1_1") (pintype "passive"))
      (node (ref "C23") (pin "1") (pinfunction "1_1") (pintype "passive"))
      (node (ref "C24") (pin "1") (pinfunction "1_1") (pintype "passive"))
      (node (ref "C3") (pin "2") (pinfunction "2_2") (pintype "passive"))
      (node (ref "C4") (pin "1") (pinfunction "1_1") (pintype "passive"))
      (node (ref "C7") (pin "1") (pinfunction "1_1") (pintype "passive"))
      (node (ref "C8") (pin "1") (pinfunction "1_1") (pintype "passive"))
      (node (ref "C9") (pin "1") (pinfunction "1_1") (pintype "passive"))
      (node (ref "D1") (pin "2") (pinfunction "K_2") (pintype "passive"))
      (node (ref "J1") (pin "4") (pinfunction "ID_4") (pintype "passive"))
      (node (ref "J1") (pin "5") (pinfunction "GND_5") (pintype "passive"))
      (node (ref "J1") (pin "6") (pinfunction "SHIELD1_6") (pintype "passive"))
      (node (ref "J1") (pin "7") (pinfunction "SHIELD2_7") (pintype "passive"))
      (node (ref "J1") (pin "8") (pinfunction "SHIELD3_8") (pintype "passive"))
      (node (ref "J1") (pin "9") (pinfunction "SHIELD4_9") (pintype "passive"))
      (node (ref "J2") (pin "4") (pinfunction "GND_4") (pintype "passive"))
      (node (ref "J2") (pin "5") (pinfunction "SHIELD1_5") (pintype "passive"))
      (node (ref "J2") (pin "6") (pinfunction "SHIELD2_6") (pintype "passive"))
      (node (ref "J4") (pin "A1") (pinfunction "GND1_A1") (pintype "passive"))
      (node (ref "J4") (pin "A12") (pinfunction "GND2_A12") (pintype "passive"))
      (node (ref "J4") (pin "B1") (pinfunction "GND3_B1") (pintype "passive"))
      (node (ref "J4") (pin "B12") (pinfunction "GND4_B12") (pintype "passive"))
      (node (ref "J4") (pin "C1") (pinfunction "SHIELD1_C1") (pintype "passive"))
      (node (ref "J4") (pin "C2") (pinfunction "SHIELD2_C2") (pintype "passive"))
      (node (ref "J4") (pin "C3") (pinfunction "SHIELD3_C3") (pintype "passive"))
      (node (ref "J4") (pin "C4") (pinfunction "SHIELD4_C4") (pintype "passive"))
      (node (ref "Q1") (pin "3") (pinfunction "S2_3") (pintype "passive"))
      (node (ref "Q2") (pin "3") (pinfunction "S2_3") (pintype "passive"))
      (node (ref "Q3") (pin "3") (pinfunction "S2_3") (pintype "passive"))
      (node (ref "Q4") (pin "3") (pinfunction "S2_3") (pintype "passive"))
      (node (ref "R12") (pin "1") (pinfunction "1_1") (pintype "passive"))
      (node (ref "R2") (pin "1") (pinfunction "1_1") (pintype "passive"))
      (node (ref "R28") (pin "1") (pinfunction "1_1") (pintype "passive"))
      (node (ref "R31") (pin "2") (pinfunction "2_2") (pintype "passive"))
      (node (ref "R33") (pin "2") (pinfunction "2_2") (pintype "passive"))
      (node (ref "R7") (pin "1") (pinfunction "1_1") (pintype "passive"))
      (node (ref "S1") (pin "2") (pinfunction "2_2") (pintype "passive"))
      (node (ref "U2") (pin "13") (pinfunction "AGND_13") (pintype "passive"))
      (node (ref "U2") (pin "24") (pinfunction "LED4/I2C_24") (pintype "passive"))
      (node (ref "U2") (pin "41") (pinfunction "EPAD_41") (pintype "passive"))
      (node (ref "U4") (pin "1") (pinfunction "VSS_1") (pintype "passive"))
      (node (ref "ZD1") (pin "1") (pinfunction "A_1") (pintype "passive"))
    )
    (net (code "43") (name "Net-(D1-A)") (class "Default")
      (node (ref "D1") (pin "1") (pinfunction "A_1") (pintype "passive"))
      (node (ref "R13") (pin "1") (pinfunction "1_1") (pintype "passive"))
    )
    (net (code "44") (name "Net-(D2-K)") (class "Default")
      (node (ref "D2") (pin "2") (pinfunction "K_2") (pintype "passive"))
      (node (ref "R14") (pin "1") (pinfunction "1_1") (pintype "passive"))
    )
    (net (code "45") (name "Net-(D3-Pad3)") (class "Default")
      (node (ref "D3") (pin "3") (pintype "passive"))
      (node (ref "R15") (pin "2") (pinfunction "2_2") (pintype "passive"))
    )
    (net (code "46") (name "Net-(J5-DM)") (class "Default")
      (node (ref "J5") (pin "2") (pinfunction "DM_2") (pintype "passive"))
      (node (ref "J5") (pin "3") (pinfunction "DP_3") (pintype "passive"))
    )
    (net (code "47") (name "Net-(J5-GND)") (class "Default")
      (node (ref "J5") (pin "4") (pinfunction "GND_4") (pintype "passive"))
      (node (ref "R16") (pin "2") (pinfunction "2_2") (pintype "passive"))
      (node (ref "R28") (pin "2") (pinfunction "2_2") (pintype "passive"))
    )
    (net (code "48") (name "Net-(J5-VBUS)") (class "Default")
      (node (ref "C22") (pin "2") (pinfunction "2_2") (pintype "passive"))
      (node (ref "J5") (pin "1") (pinfunction "VBUS_1") (pintype "passive"))
      (node (ref "Q10") (pin "3") (pinfunction "D_3") (pintype "passive"))
      (node (ref "R17") (pin "1") (pinfunction "1_1") (pintype "passive"))
      (node (ref "R18") (pin "2") (pinfunction "2_2") (pintype "passive"))
    )
    (net (code "49") (name "Net-(J6-Pad1)") (class "Default")
      (node (ref "J6") (pin "1") (pinfunction "1_1") (pintype "passive"))
      (node (ref "R23") (pin "1") (pinfunction "1_1") (pintype "passive"))
    )
    (net (code "50") (name "Net-(J6-Pad2)") (class "Default")
      (node (ref "J6") (pin "2") (pinfunction "2_2") (pintype "passive"))
      (node (ref "R24") (pin "1") (pinfunction "1_1") (pintype "passive"))
    )
    (net (code "51") (name "Net-(J6-Pad3)") (class "Default")
      (node (ref "J6") (pin "3") (pinfunction "3_3") (pintype "passive"))
      (node (ref "R25") (pin "1") (pinfunction "1_1") (pintype "passive"))
    )
    (net (code "52") (name "Net-(J6-Pad4)") (class "Default")
      (node (ref "J6") (pin "4") (pinfunction "4_4") (pintype "passive"))
      (node (ref "R26") (pin "1") (pinfunction "1_1") (pintype "passive"))
    )
    (net (code "53") (name "Net-(J6-Pad5)") (class "Default")
      (node (ref "J6") (pin "5") (pinfunction "5_5") (pintype "passive"))
      (node (ref "R29") (pin "1") (pinfunction "1_1") (pintype "passive"))
    )
    (net (code "54") (name "Net-(J6-Pad6)") (class "Default")
      (node (ref "J6") (pin "6") (pinfunction "6_6") (pintype "passive"))
      (node (ref "R30") (pin "1") (pinfunction "1_1") (pintype "passive"))
    )
    (net (code "55") (name "Net-(Q1-D1)") (class "Default")
      (node (ref "Q1") (pin "2") (pinfunction "D1_2") (pintype "passive"))
      (node (ref "Q2") (pin "5") (pinfunction "D2_5") (pintype "passive"))
    )
    (net (code "56") (name "Net-(Q1-G1)") (class "Default")
      (node (ref "Q1") (pin "6") (pinfunction "G1_6") (pintype "passive"))
      (node (ref "Q2") (pin "6") (pinfunction "G1_6") (pintype "passive"))
      (node (ref "Q3") (pin "6") (pinfunction "G1_6") (pintype "passive"))
      (node (ref "Q4") (pin "6") (pinfunction "G1_6") (pintype "passive"))
      (node (ref "U1") (pin "1") (pinfunction "OD_1") (pintype "passive"))
    )
    (net (code "57") (name "Net-(Q1-G2)") (class "Default")
      (node (ref "Q1") (pin "4") (pinfunction "G2_4") (pintype "passive"))
      (node (ref "Q2") (pin "4") (pinfunction "G2_4") (pintype "passive"))
      (node (ref "Q3") (pin "4") (pinfunction "G2_4") (pintype "passive"))
      (node (ref "Q4") (pin "4") (pinfunction "G2_4") (pintype "passive"))
      (node (ref "U1") (pin "3") (pinfunction "OC_3") (pintype "passive"))
    )
    (net (code "58") (name "Net-(Q2-D1)") (class "Default")
      (node (ref "Q2") (pin "2") (pinfunction "D1_2") (pintype "passive"))
      (node (ref "Q3") (pin "5") (pinfunction "D2_5") (pintype "passive"))
    )
    (net (code "59") (name "Net-(Q3-D1)") (class "Default")
      (node (ref "Q3") (pin "2") (pinfunction "D1_2") (pintype "passive"))
      (node (ref "Q4") (pin "5") (pinfunction "D2_5") (pintype "passive"))
    )
    (net (code "60") (name "Net-(Q10-G)") (class "Default")
      (node (ref "Q10") (pin "1") (pinfunction "G_1") (pintype "passive"))
      (node (ref "Q11") (pin "3") (pinfunction "D_3") (pintype "passive"))
      (node (ref "Q12") (pin "1") (pinfunction "G_1") (pintype "passive"))
      (node (ref "R31") (pin "1") (pinfunction "1_1") (pintype "passive"))
    )
    (net (code "61") (name "Net-(Q11-G)") (class "Default")
      (node (ref "Q11") (pin "1") (pinfunction "G_1") (pintype "passive"))
      (node (ref "R27") (pin "2") (pinfunction "2_2") (pintype "passive"))
      (node (ref "R33") (pin "1") (pinfunction "1_1") (pintype "passive"))
    )
    (net (code "62") (name "Net-(Q12-S)") (class "Default")
      (node (ref "Q12") (pin "2") (pinfunction "S_2") (pintype "passive"))
      (node (ref "R17") (pin "2") (pinfunction "2_2") (pintype "passive"))
    )
    (net (code "63") (name "Net-(U1-CS)") (class "Default")
      (node (ref "R2") (pin "2") (pinfunction "2_2") (pintype "passive"))
      (node (ref "U1") (pin "2") (pinfunction "CS_2") (pintype "passive"))
    )
    (net (code "64") (name "Net-(U1-VCC)") (class "Default")
      (node (ref "C1") (pin "2") (pinfunction "2_2") (pintype "passive"))
      (node (ref "R1") (pin "1") (pinfunction "1_1") (pintype "passive"))
      (node (ref "U1") (pin "5") (pinfunction "VCC_5") (pintype "passive"))
    )
    (net (code "65") (name "unconnected-(J4-SBU1-PadA8)") (class "Default")
      (node (ref "J4") (pin "A8") (pinfunction "SBU1_A8") (pintype "passive"))
    )
    (net (code "66") (name "unconnected-(J4-SBU2-PadB8)") (class "Default")
      (node (ref "J4") (pin "B8") (pinfunction "SBU2_B8") (pintype "passive"))
    )
    (net (code "67") (name "unconnected-(J4-SSRXn1-PadB10)") (class "Default")
      (node (ref "J4") (pin "B10") (pinfunction "SSRXn1_B10") (pintype "passive"))
    )
    (net (code "68") (name "unconnected-(J4-SSRXn2-PadA10)") (class "Default")
      (node (ref "J4") (pin "A10") (pinfunction "SSRXn2_A10") (pintype "passive"))
    )
    (net (code "69") (name "unconnected-(J4-SSRXp1-PadB11)") (class "Default")
      (node (ref "J4") (pin "B11") (pinfunction "SSRXp1_B11") (pintype "passive"))
    )
    (net (code "70") (name "unconnected-(J4-SSRXp2-PadA11)") (class "Default")
      (node (ref "J4") (pin "A11") (pinfunction "SSRXp2_A11") (pintype "passive"))
    )
    (net (code "71") (name "unconnected-(J4-SSTXn1-PadA3)") (class "Default")
      (node (ref "J4") (pin "A3") (pinfunction "SSTXn1_A3") (pintype "passive"))
    )
    (net (code "72") (name "unconnected-(J4-SSTXn2-PadB3)") (class "Default")
      (node (ref "J4") (pin "B3") (pinfunction "SSTXn2_B3") (pintype "passive"))
    )
    (net (code "73") (name "unconnected-(J4-SSTXp1-PadA2)") (class "Default")
      (node (ref "J4") (pin "A2") (pinfunction "SSTXp1_A2") (pintype "passive"))
    )
    (net (code "74") (name "unconnected-(J4-SSTXp2-PadB2)") (class "Default")
      (node (ref "J4") (pin "B2") (pinfunction "SSTXp2_B2") (pintype "passive"))
    )
    (net (code "75") (name "unconnected-(J5-SHIELD1-Pad5)") (class "Default")
      (node (ref "J5") (pin "5") (pinfunction "SHIELD1_5") (pintype "passive"))
    )
    (net (code "76") (name "unconnected-(J5-SHIELD2-Pad6)") (class "Default")
      (node (ref "J5") (pin "6") (pinfunction "SHIELD2_6") (pintype "passive"))
    )
    (net (code "77") (name "unconnected-(Q1-D2-Pad5)") (class "Default")
      (node (ref "Q1") (pin "5") (pinfunction "D2_5") (pintype "passive"))
    )
    (net (code "78") (name "unconnected-(Q4-D1-Pad2)") (class "Default")
      (node (ref "Q4") (pin "2") (pinfunction "D1_2") (pintype "passive"))
    )
    (net (code "79") (name "unconnected-(Q5-D1-Pad2)") (class "Default")
      (node (ref "Q5") (pin "2") (pinfunction "D1_2") (pintype "passive"))
    )
    (net (code "80") (name "unconnected-(Q6-D1-Pad2)") (class "Default")
      (node (ref "Q6") (pin "2") (pinfunction "D1_2") (pintype "passive"))
    )
    (net (code "81") (name "unconnected-(Q8-D1-Pad2)") (class "Default")
      (node (ref "Q8") (pin "2") (pinfunction "D1_2") (pintype "passive"))
    )
    (net (code "82") (name "unconnected-(U1-TD-Pad4)") (class "Default")
      (node (ref "U1") (pin "4") (pinfunction "TD_4") (pintype "passive"))
    )
    (net (code "83") (name "unconnected-(U4-PA2-Pad4)") (class "Default")
      (node (ref "U4") (pin "4") (pinfunction "PA2_4") (pintype "passive"))
    )
    (net (code "84") (name "unconnected-(U4-PB3-Pad9)") (class "Default")
      (node (ref "U4") (pin "9") (pinfunction "PB3_9") (pintype "passive"))
    )
  )
)
